# Flight_Controller.net
KiCad netlist of a schematic drawn in EAGLE
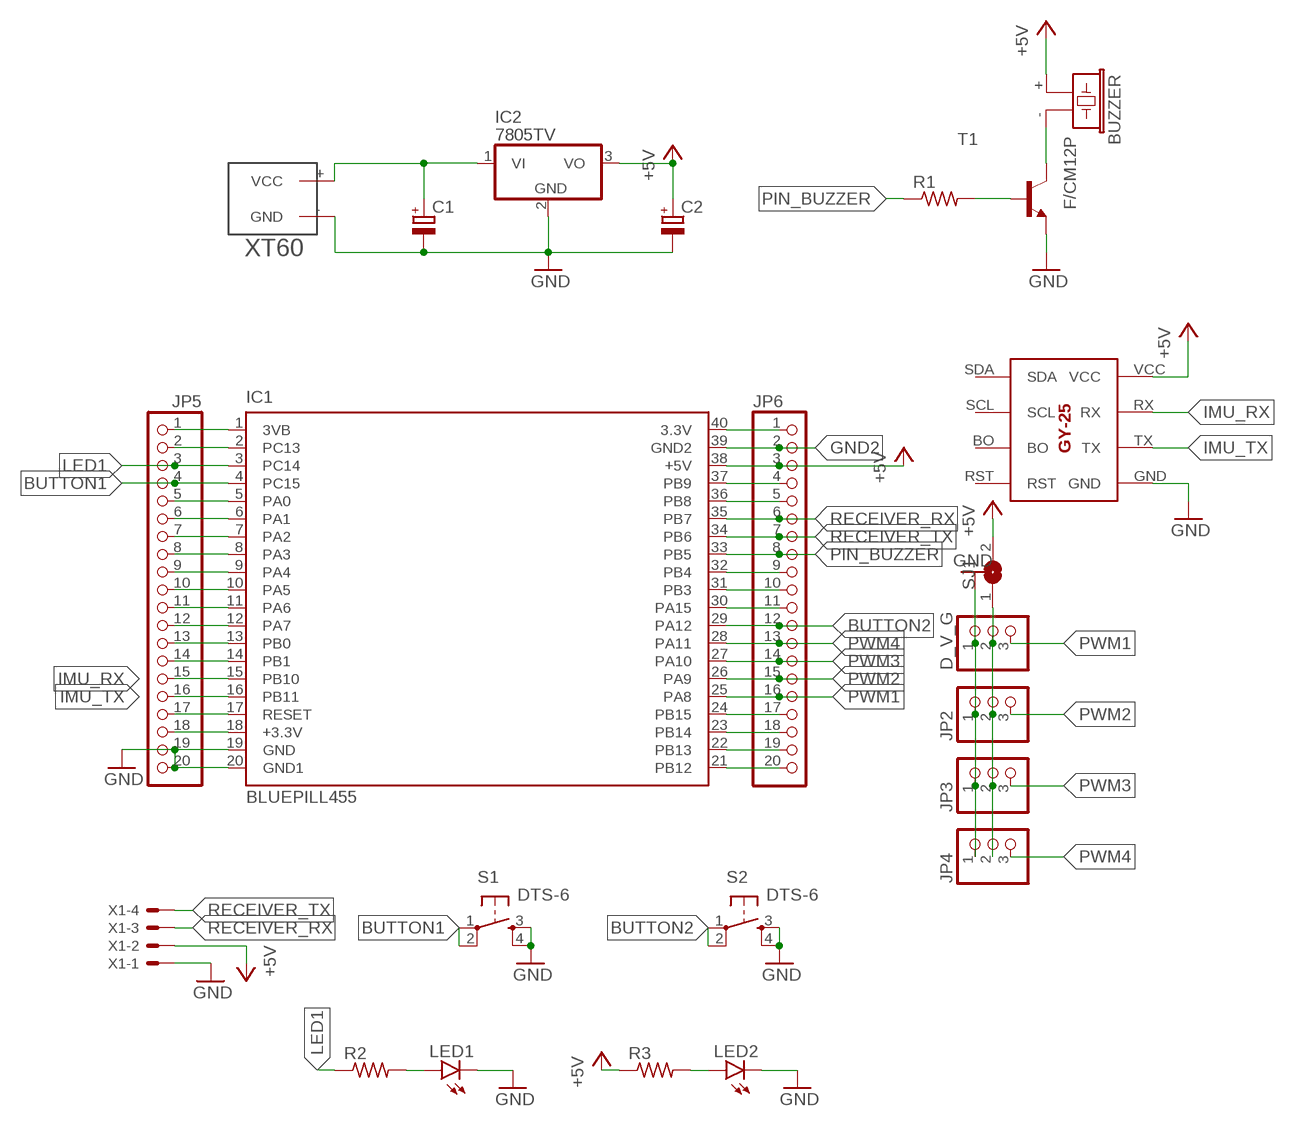
[diagram p0: schematic, sheet 1]

(export (version "E")
  (design (tool "Eeschema 10.0.6"))
  (components
    (comp (ref "BUZZER")
      (value "F/CM12P")
      (footprint "eagle-import:F_CM12P")
      (libsource (lib "eagle-import") (part "F/CM12P"))
    )
    (comp (ref "C1")
      (value "CPOL-EUE2,5-6E")
      (footprint "eagle-import:E2,5-6E")
      (libsource (lib "eagle-import") (part "CPOL-EUE2,5-6E"))
    )
    (comp (ref "C2")
      (value "CPOL-EUE2,5-6E")
      (footprint "eagle-import:E2,5-6E")
      (libsource (lib "eagle-import") (part "CPOL-EUE2,5-6E"))
    )
    (comp (ref "D_V_G")
      (value "PINHD-1X3")
      (footprint "eagle-import:1X03")
      (libsource (lib "eagle-import") (part "PINHD-1X3"))
    )
    (comp (ref "GY-1")
      (value "GY-25GY-25_INV")
      (footprint "eagle-import:GY-25_INV")
      (libsource (lib "eagle-import") (part "GY-25GY-25_INV"))
    )
    (comp (ref "IC1")
      (value "BLUEPILL455")
      (footprint "eagle-import:DIL40")
      (fields (field (name "MF") "BluePill"))
      (libsource (lib "eagle-import") (part "BLUEPILL455"))
    )
    (comp (ref "IC2")
      (value "7805TV")
      (footprint "eagle-import:TO220V")
      (libsource (lib "eagle-import") (part "78TV05"))
    )
    (comp (ref "JP2")
      (value "PINHD-1X3")
      (footprint "eagle-import:1X03")
      (libsource (lib "eagle-import") (part "PINHD-1X3"))
    )
    (comp (ref "JP3")
      (value "PINHD-1X3")
      (footprint "eagle-import:1X03")
      (libsource (lib "eagle-import") (part "PINHD-1X3"))
    )
    (comp (ref "JP4")
      (value "PINHD-1X3")
      (footprint "eagle-import:1X03")
      (libsource (lib "eagle-import") (part "PINHD-1X3"))
    )
    (comp (ref "JP5")
      (value "PINHD-1X20")
      (footprint "eagle-import:1X20")
      (libsource (lib "eagle-import") (part "PINHD-1X20"))
    )
    (comp (ref "JP6")
      (value "PINHD-1X20")
      (footprint "eagle-import:1X20")
      (libsource (lib "eagle-import") (part "PINHD-1X20"))
    )
    (comp (ref "LED1")
      (value "LED3MM")
      (footprint "eagle-import:LED3MM")
      (libsource (lib "eagle-import") (part "LED3MM"))
    )
    (comp (ref "LED2")
      (value "LED3MM")
      (footprint "eagle-import:LED3MM")
      (libsource (lib "eagle-import") (part "LED3MM"))
    )
    (comp (ref "R1")
      (value "R-US_M0805")
      (footprint "eagle-import:M0805")
      (libsource (lib "eagle-import") (part "R-US_M0805"))
    )
    (comp (ref "R2")
      (value "R-US_M0805")
      (footprint "eagle-import:M0805")
      (libsource (lib "eagle-import") (part "R-US_M0805"))
    )
    (comp (ref "R3")
      (value "R-US_M0805")
      (footprint "eagle-import:M0805")
      (libsource (lib "eagle-import") (part "R-US_M0805"))
    )
    (comp (ref "S1")
      (value "DTS-6")
      (footprint "eagle-import:DTS-6")
      (libsource (lib "eagle-import") (part "DTS-6"))
    )
    (comp (ref "S2")
      (value "DTS-6")
      (footprint "eagle-import:DTS-6")
      (libsource (lib "eagle-import") (part "DTS-6"))
    )
    (comp (ref "SJ1") (value "SJ") (footprint "eagle-import:SJ") (libsource (lib "eagle-import") (part "SJ")))
    (comp (ref "T1")
      (value "-NPN-TO92-EBC")
      (footprint "eagle-import:TO92-EBC")
      (libsource (lib "eagle-import") (part "-NPN-TO92-EBC"))
    )
    (comp (ref "U$1")
      (value "XT60")
      (footprint "eagle-import:XT60")
      (libsource (lib "eagle-import") (part "XT60"))
    )
    (comp (ref "X1")
      (value "KK-156-4")
      (footprint "eagle-import:KK-156-4")
      (fields (field (name "MF") "MOLEX"))
      (libsource (lib "eagle-import") (part "KK-156-4"))
    )
  )
  (nets
    (net (code "1") (name "+5V") (class "Default")
      (node (ref "BUZZER") (pin "+") (pinfunction "1_+") (pintype "passive"))
      (node (ref "C2") (pin "+") (pinfunction "+_+") (pintype "passive"))
      (node (ref "GY-1") (pin "VCC") (pinfunction "VCC_VCC") (pintype "bidirectional"))
      (node (ref "IC1") (pin "38") (pinfunction "+5V_38") (pintype "bidirectional"))
      (node (ref "IC2") (pin "3") (pinfunction "VO_3") (pintype "passive"))
      (node (ref "JP6") (pin "3") (pinfunction "3_3") (pintype "passive"))
      (node (ref "R3") (pin "1") (pinfunction "1_1") (pintype "passive"))
      (node (ref "SJ1") (pin "2") (pinfunction "2_2") (pintype "passive"))
      (node (ref "X1") (pin "2") (pinfunction "S_2") (pintype "passive"))
    )
    (net (code "2") (name "BUTTON1") (class "Default")
      (node (ref "IC1") (pin "4") (pinfunction "PC15_4") (pintype "bidirectional"))
      (node (ref "JP5") (pin "4") (pinfunction "4_4") (pintype "passive"))
      (node (ref "S1") (pin "1") (pinfunction "1_1") (pintype "passive"))
      (node (ref "S1") (pin "2") (pinfunction "2_2") (pintype "passive"))
    )
    (net (code "3") (name "BUTTON2") (class "Default")
      (node (ref "IC1") (pin "29") (pinfunction "PA12_29") (pintype "bidirectional"))
      (node (ref "JP6") (pin "12") (pinfunction "12_12") (pintype "passive"))
      (node (ref "S2") (pin "1") (pinfunction "1_1") (pintype "passive"))
      (node (ref "S2") (pin "2") (pinfunction "2_2") (pintype "passive"))
    )
    (net (code "4") (name "GND") (class "Default")
      (node (ref "C1") (pin "-") (pinfunction "-_-") (pintype "passive"))
      (node (ref "C2") (pin "-") (pinfunction "-_-") (pintype "passive"))
      (node (ref "D_V_G") (pin "1") (pinfunction "1_1") (pintype "passive"))
      (node (ref "GY-1") (pin "GND") (pinfunction "GND_GND") (pintype "bidirectional"))
      (node (ref "IC1") (pin "19") (pinfunction "GND_19") (pintype "bidirectional"))
      (node (ref "IC1") (pin "20") (pinfunction "GND1_20") (pintype "bidirectional"))
      (node (ref "IC2") (pin "2") (pinfunction "GND_2") (pintype "passive"))
      (node (ref "JP2") (pin "1") (pinfunction "1_1") (pintype "passive"))
      (node (ref "JP3") (pin "1") (pinfunction "1_1") (pintype "passive"))
      (node (ref "JP4") (pin "1") (pinfunction "1_1") (pintype "passive"))
      (node (ref "JP5") (pin "19") (pinfunction "19_19") (pintype "passive"))
      (node (ref "JP5") (pin "20") (pinfunction "20_20") (pintype "passive"))
      (node (ref "LED1") (pin "K") (pinfunction "C_K") (pintype "passive"))
      (node (ref "LED2") (pin "K") (pinfunction "C_K") (pintype "passive"))
      (node (ref "S1") (pin "3") (pinfunction "3_3") (pintype "passive"))
      (node (ref "S1") (pin "4") (pinfunction "4_4") (pintype "passive"))
      (node (ref "S2") (pin "3") (pinfunction "3_3") (pintype "passive"))
      (node (ref "S2") (pin "4") (pinfunction "4_4") (pintype "passive"))
      (node (ref "T1") (pin "E") (pinfunction "E_E") (pintype "passive"))
      (node (ref "U$1") (pin "-") (pinfunction "GND_-") (pintype "bidirectional"))
      (node (ref "X1") (pin "1") (pinfunction "S_1") (pintype "passive"))
    )
    (net (code "5") (name "GND2") (class "Default")
      (node (ref "IC1") (pin "39") (pinfunction "GND2_39") (pintype "bidirectional"))
      (node (ref "JP6") (pin "2") (pinfunction "2_2") (pintype "passive"))
    )
    (net (code "6") (name "IMU_RX") (class "Default")
      (node (ref "GY-1") (pin "RX") (pinfunction "RX_RX") (pintype "bidirectional"))
      (node (ref "IC1") (pin "15") (pinfunction "PB10_15") (pintype "bidirectional"))
      (node (ref "JP5") (pin "15") (pinfunction "15_15") (pintype "passive"))
    )
    (net (code "7") (name "IMU_TX") (class "Default")
      (node (ref "GY-1") (pin "TX") (pinfunction "TX_TX") (pintype "bidirectional"))
      (node (ref "IC1") (pin "16") (pinfunction "PB11_16") (pintype "bidirectional"))
      (node (ref "JP5") (pin "16") (pinfunction "16_16") (pintype "passive"))
    )
    (net (code "8") (name "LED1") (class "Default")
      (node (ref "IC1") (pin "3") (pinfunction "PC14_3") (pintype "bidirectional"))
      (node (ref "JP5") (pin "3") (pinfunction "3_3") (pintype "passive"))
      (node (ref "R2") (pin "1") (pinfunction "1_1") (pintype "passive"))
    )
    (net (code "9") (name "Net-(BUZZER-2)") (class "Default")
      (node (ref "BUZZER") (pin "-") (pinfunction "2_-") (pintype "passive"))
      (node (ref "T1") (pin "C") (pinfunction "C_C") (pintype "passive"))
    )
    (net (code "10") (name "Net-(D_V_G-Pad2)") (class "Default")
      (node (ref "D_V_G") (pin "2") (pinfunction "2_2") (pintype "passive"))
      (node (ref "JP2") (pin "2") (pinfunction "2_2") (pintype "passive"))
      (node (ref "JP3") (pin "2") (pinfunction "2_2") (pintype "passive"))
      (node (ref "JP4") (pin "2") (pinfunction "2_2") (pintype "passive"))
      (node (ref "SJ1") (pin "1") (pinfunction "1_1") (pintype "passive"))
    )
    (net (code "11") (name "Net-(IC1-+3.3V)") (class "Default")
      (node (ref "IC1") (pin "18") (pinfunction "+3.3V_18") (pintype "bidirectional"))
      (node (ref "JP5") (pin "18") (pinfunction "18_18") (pintype "passive"))
    )
    (net (code "12") (name "Net-(IC1-3.3V)") (class "Default")
      (node (ref "IC1") (pin "40") (pinfunction "3.3V_40") (pintype "bidirectional"))
      (node (ref "JP6") (pin "1") (pinfunction "1_1") (pintype "passive"))
    )
    (net (code "13") (name "Net-(IC1-3VB)") (class "Default")
      (node (ref "IC1") (pin "1") (pinfunction "3VB_1") (pintype "input"))
      (node (ref "JP5") (pin "1") (pinfunction "1_1") (pintype "passive"))
    )
    (net (code "14") (name "Net-(IC1-PA0)") (class "Default")
      (node (ref "IC1") (pin "5") (pinfunction "PA0_5") (pintype "bidirectional"))
      (node (ref "JP5") (pin "5") (pinfunction "5_5") (pintype "passive"))
    )
    (net (code "15") (name "Net-(IC1-PA1)") (class "Default")
      (node (ref "IC1") (pin "6") (pinfunction "PA1_6") (pintype "bidirectional"))
      (node (ref "JP5") (pin "6") (pinfunction "6_6") (pintype "passive"))
    )
    (net (code "16") (name "Net-(IC1-PA2)") (class "Default")
      (node (ref "IC1") (pin "7") (pinfunction "PA2_7") (pintype "bidirectional"))
      (node (ref "JP5") (pin "7") (pinfunction "7_7") (pintype "passive"))
    )
    (net (code "17") (name "Net-(IC1-PA3)") (class "Default")
      (node (ref "IC1") (pin "8") (pinfunction "PA3_8") (pintype "bidirectional"))
      (node (ref "JP5") (pin "8") (pinfunction "8_8") (pintype "passive"))
    )
    (net (code "18") (name "Net-(IC1-PA4)") (class "Default")
      (node (ref "IC1") (pin "9") (pinfunction "PA4_9") (pintype "bidirectional"))
      (node (ref "JP5") (pin "9") (pinfunction "9_9") (pintype "passive"))
    )
    (net (code "19") (name "Net-(IC1-PA5)") (class "Default")
      (node (ref "IC1") (pin "10") (pinfunction "PA5_10") (pintype "bidirectional"))
      (node (ref "JP5") (pin "10") (pinfunction "10_10") (pintype "passive"))
    )
    (net (code "20") (name "Net-(IC1-PA6)") (class "Default")
      (node (ref "IC1") (pin "11") (pinfunction "PA6_11") (pintype "power_in"))
      (node (ref "JP5") (pin "11") (pinfunction "11_11") (pintype "passive"))
    )
    (net (code "21") (name "Net-(IC1-PA7)") (class "Default")
      (node (ref "IC1") (pin "12") (pinfunction "PA7_12") (pintype "power_in"))
      (node (ref "JP5") (pin "12") (pinfunction "12_12") (pintype "passive"))
    )
    (net (code "22") (name "Net-(IC1-PA15)") (class "Default")
      (node (ref "IC1") (pin "30") (pinfunction "PA15_30") (pintype "bidirectional"))
      (node (ref "JP6") (pin "11") (pinfunction "11_11") (pintype "passive"))
    )
    (net (code "23") (name "Net-(IC1-PB0)") (class "Default")
      (node (ref "IC1") (pin "13") (pinfunction "PB0_13") (pintype "input"))
      (node (ref "JP5") (pin "13") (pinfunction "13_13") (pintype "passive"))
    )
    (net (code "24") (name "Net-(IC1-PB1)") (class "Default")
      (node (ref "IC1") (pin "14") (pinfunction "PB1_14") (pintype "output"))
      (node (ref "JP5") (pin "14") (pinfunction "14_14") (pintype "passive"))
    )
    (net (code "25") (name "Net-(IC1-PB3)") (class "Default")
      (node (ref "IC1") (pin "31") (pinfunction "PB3_31") (pintype "power_in"))
      (node (ref "JP6") (pin "10") (pinfunction "10_10") (pintype "passive"))
    )
    (net (code "26") (name "Net-(IC1-PB4)") (class "Default")
      (node (ref "IC1") (pin "32") (pinfunction "PB4_32") (pintype "power_in"))
      (node (ref "JP6") (pin "9") (pinfunction "9_9") (pintype "passive"))
    )
    (net (code "27") (name "Net-(IC1-PB8)") (class "Default")
      (node (ref "IC1") (pin "36") (pinfunction "PB8_36") (pintype "bidirectional"))
      (node (ref "JP6") (pin "5") (pinfunction "5_5") (pintype "passive"))
    )
    (net (code "28") (name "Net-(IC1-PB9)") (class "Default")
      (node (ref "IC1") (pin "37") (pinfunction "PB9_37") (pintype "bidirectional"))
      (node (ref "JP6") (pin "4") (pinfunction "4_4") (pintype "passive"))
    )
    (net (code "29") (name "Net-(IC1-PB12)") (class "Default")
      (node (ref "IC1") (pin "21") (pinfunction "PB12_21") (pintype "bidirectional"))
      (node (ref "JP6") (pin "20") (pinfunction "20_20") (pintype "passive"))
    )
    (net (code "30") (name "Net-(IC1-PB13)") (class "Default")
      (node (ref "IC1") (pin "22") (pinfunction "PB13_22") (pintype "bidirectional"))
      (node (ref "JP6") (pin "19") (pinfunction "19_19") (pintype "passive"))
    )
    (net (code "31") (name "Net-(IC1-PB14)") (class "Default")
      (node (ref "IC1") (pin "23") (pinfunction "PB14_23") (pintype "bidirectional"))
      (node (ref "JP6") (pin "18") (pinfunction "18_18") (pintype "passive"))
    )
    (net (code "32") (name "Net-(IC1-PB15)") (class "Default")
      (node (ref "IC1") (pin "24") (pinfunction "PB15_24") (pintype "bidirectional"))
      (node (ref "JP6") (pin "17") (pinfunction "17_17") (pintype "passive"))
    )
    (net (code "33") (name "Net-(IC1-PC13)") (class "Default")
      (node (ref "IC1") (pin "2") (pinfunction "PC13_2") (pintype "bidirectional"))
      (node (ref "JP5") (pin "2") (pinfunction "2_2") (pintype "passive"))
    )
    (net (code "34") (name "Net-(IC1-RESET)") (class "Default")
      (node (ref "IC1") (pin "17") (pinfunction "RESET_17") (pintype "bidirectional"))
      (node (ref "JP5") (pin "17") (pinfunction "17_17") (pintype "passive"))
    )
    (net (code "35") (name "Net-(IC2-VI)") (class "Default")
      (node (ref "C1") (pin "+") (pinfunction "+_+") (pintype "passive"))
      (node (ref "IC2") (pin "1") (pinfunction "VI_1") (pintype "input"))
      (node (ref "U$1") (pin "+") (pinfunction "VCC_+") (pintype "bidirectional"))
    )
    (net (code "36") (name "Net-(LED1-PadA)") (class "Default")
      (node (ref "LED1") (pin "A") (pinfunction "A_A") (pintype "passive"))
      (node (ref "R2") (pin "2") (pinfunction "2_2") (pintype "passive"))
    )
    (net (code "37") (name "Net-(LED2-PadA)") (class "Default")
      (node (ref "LED2") (pin "A") (pinfunction "A_A") (pintype "passive"))
      (node (ref "R3") (pin "2") (pinfunction "2_2") (pintype "passive"))
    )
    (net (code "38") (name "Net-(R1-Pad2)") (class "Default")
      (node (ref "R1") (pin "2") (pinfunction "2_2") (pintype "passive"))
      (node (ref "T1") (pin "B") (pinfunction "B_B") (pintype "passive"))
    )
    (net (code "39") (name "PIN_BUZZER") (class "Default")
      (node (ref "IC1") (pin "33") (pinfunction "PB5_33") (pintype "bidirectional"))
      (node (ref "JP6") (pin "8") (pinfunction "8_8") (pintype "passive"))
      (node (ref "R1") (pin "1") (pinfunction "1_1") (pintype "passive"))
    )
    (net (code "40") (name "PWM1") (class "Default")
      (node (ref "D_V_G") (pin "3") (pinfunction "3_3") (pintype "passive"))
      (node (ref "IC1") (pin "25") (pinfunction "PA8_25") (pintype "bidirectional"))
      (node (ref "JP6") (pin "16") (pinfunction "16_16") (pintype "passive"))
    )
    (net (code "41") (name "PWM2") (class "Default")
      (node (ref "IC1") (pin "26") (pinfunction "PA9_26") (pintype "bidirectional"))
      (node (ref "JP2") (pin "3") (pinfunction "3_3") (pintype "passive"))
      (node (ref "JP6") (pin "15") (pinfunction "15_15") (pintype "passive"))
    )
    (net (code "42") (name "PWM3") (class "Default")
      (node (ref "IC1") (pin "27") (pinfunction "PA10_27") (pintype "bidirectional"))
      (node (ref "JP3") (pin "3") (pinfunction "3_3") (pintype "passive"))
      (node (ref "JP6") (pin "14") (pinfunction "14_14") (pintype "passive"))
    )
    (net (code "43") (name "PWM4") (class "Default")
      (node (ref "IC1") (pin "28") (pinfunction "PA11_28") (pintype "bidirectional"))
      (node (ref "JP4") (pin "3") (pinfunction "3_3") (pintype "passive"))
      (node (ref "JP6") (pin "13") (pinfunction "13_13") (pintype "passive"))
    )
    (net (code "44") (name "RECEIVER_RX") (class "Default")
      (node (ref "IC1") (pin "35") (pinfunction "PB7_35") (pintype "bidirectional"))
      (node (ref "JP6") (pin "6") (pinfunction "6_6") (pintype "passive"))
      (node (ref "X1") (pin "3") (pinfunction "S_3") (pintype "passive"))
    )
    (net (code "45") (name "RECEIVER_TX") (class "Default")
      (node (ref "IC1") (pin "34") (pinfunction "PB6_34") (pintype "bidirectional"))
      (node (ref "JP6") (pin "7") (pinfunction "7_7") (pintype "passive"))
      (node (ref "X1") (pin "4") (pinfunction "S_4") (pintype "passive"))
    )
    (net (code "46") (name "unconnected-(GY-1-PadBO)") (class "Default")
      (node (ref "GY-1") (pin "BO") (pinfunction "BO_BO") (pintype "bidirectional"))
    )
    (net (code "47") (name "unconnected-(GY-1-PadRST)") (class "Default")
      (node (ref "GY-1") (pin "RST") (pinfunction "RST_RST") (pintype "bidirectional"))
    )
    (net (code "48") (name "unconnected-(GY-1-PadSCL)") (class "Default")
      (node (ref "GY-1") (pin "SCL") (pinfunction "SCL_SCL") (pintype "bidirectional"))
    )
    (net (code "49") (name "unconnected-(GY-1-PadSDA)") (class "Default")
      (node (ref "GY-1") (pin "SDA") (pinfunction "SDA_SDA") (pintype "bidirectional"))
    )
  )
)
